# Rele_WIFI_6_Board.net
KiCad netlist of a schematic drawn in EAGLE
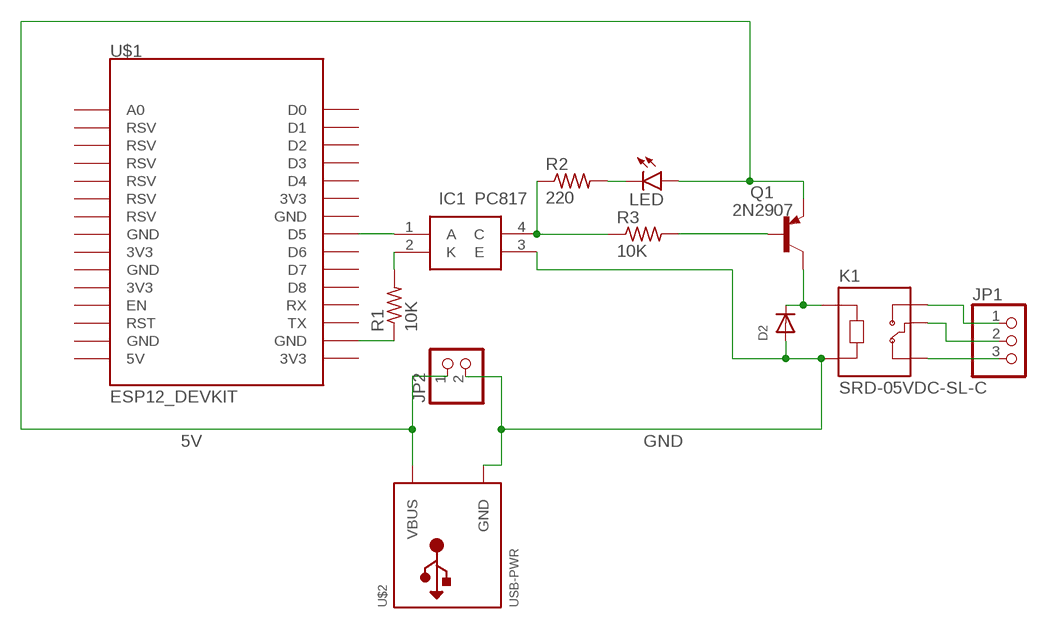
[diagram p0: schematic, sheet 1]

(export (version "E")
  (design (tool "Eeschema 10.0.6"))
  (components
    (comp (ref "D2")
      (value "DIODEDO-1N4148")
      (footprint "eagle-import:DO-1N4148")
      (libsource (lib "eagle-import") (part "DIODEDO-1N4148"))
    )
    (comp (ref "IC1")
      (value "PC817")
      (footprint "eagle-import:DIP810W60P254L460H500Q4N")
      (libsource (lib "eagle-import") (part "PC817"))
    )
    (comp (ref "JP1")
      (value "PINHD-1X3")
      (footprint "eagle-import:1X03")
      (libsource (lib "eagle-import") (part "PINHD-1X3"))
    )
    (comp (ref "JP2")
      (value "PINHD-1X2")
      (footprint "eagle-import:1X02")
      (libsource (lib "eagle-import") (part "PINHD-1X2"))
    )
    (comp (ref "K1")
      (value "SRD-05VDC-SL-C")
      (footprint "eagle-import:RELAY_SRD-05VDC-SL-C")
      (fields (field (name "MF") "Songle Relay"))
      (libsource (lib "eagle-import") (part "SRD-05VDC-SL-C"))
    )
    (comp (ref "LED")
      (value "LED5MM")
      (footprint "eagle-import:LED5MM")
      (libsource (lib "eagle-import") (part "LED5MM"))
    )
    (comp (ref "Q1")
      (value "2N2907")
      (footprint "eagle-import:TO92-EBC-OVAL")
      (libsource (lib "eagle-import") (part "2N2907"))
    )
    (comp (ref "R1")
      (value "10K")
      (footprint "eagle-import:0309_12")
      (libsource (lib "eagle-import") (part "R-US_0309/12"))
    )
    (comp (ref "R2")
      (value "220")
      (footprint "eagle-import:0309_12")
      (libsource (lib "eagle-import") (part "R-US_0309/12"))
    )
    (comp (ref "R3")
      (value "10K")
      (footprint "eagle-import:0309_12")
      (libsource (lib "eagle-import") (part "R-US_0309/12"))
    )
    (comp (ref "U$1")
      (value "ESP12_DEVKIT")
      (footprint "eagle-import:ESP12_DEVKIT")
      (libsource (lib "eagle-import") (part "ESP12_DEVKIT"))
    )
    (comp (ref "U$2")
      (value "USB-PWR")
      (footprint "eagle-import:USB-MINIB-THM-MOLEX-PWRONLY")
      (libsource (lib "eagle-import") (part "USB-PWR"))
    )
  )
  (nets
    (net (code "1") (name "/5V") (class "Default")
      (node (ref "JP2") (pin "1") (pinfunction "1_1") (pintype "passive"))
      (node (ref "LED") (pin "A") (pinfunction "A_A") (pintype "passive"))
      (node (ref "Q1") (pin "E") (pinfunction "E_E") (pintype "passive"))
      (node (ref "U$2") (pin "VBUS") (pinfunction "VBUS_VBUS") (pintype "power_in"))
    )
    (net (code "2") (name "/GND") (class "Default")
      (node (ref "D2") (pin "A") (pinfunction "A_A") (pintype "passive"))
      (node (ref "IC1") (pin "3") (pinfunction "E_3") (pintype "bidirectional"))
      (node (ref "JP2") (pin "2") (pinfunction "2_2") (pintype "passive"))
      (node (ref "K1") (pin "A2") (pinfunction "A2_A2") (pintype "passive"))
      (node (ref "U$2") (pin "GND") (pinfunction "GND_GND") (pintype "power_in"))
    )
    (net (code "3") (name "Net-(D2-PadC)") (class "Default")
      (node (ref "D2") (pin "C") (pinfunction "C_C") (pintype "passive"))
      (node (ref "K1") (pin "A1") (pinfunction "A1_A1") (pintype "passive"))
      (node (ref "Q1") (pin "C") (pinfunction "C_C") (pintype "passive"))
    )
    (net (code "4") (name "Net-(IC1-A)") (class "Default")
      (node (ref "IC1") (pin "1") (pinfunction "A_1") (pintype "bidirectional"))
      (node (ref "U$1") (pin "D5") (pinfunction "D5_D5") (pintype "bidirectional"))
    )
    (net (code "5") (name "Net-(IC1-C)") (class "Default")
      (node (ref "IC1") (pin "4") (pinfunction "C_4") (pintype "bidirectional"))
      (node (ref "R2") (pin "1") (pinfunction "1_1") (pintype "passive"))
      (node (ref "R3") (pin "1") (pinfunction "1_1") (pintype "passive"))
    )
    (net (code "6") (name "Net-(IC1-K)") (class "Default")
      (node (ref "IC1") (pin "2") (pinfunction "K_2") (pintype "bidirectional"))
      (node (ref "R1") (pin "2") (pinfunction "2_2") (pintype "passive"))
    )
    (net (code "7") (name "Net-(JP1-Pad1)") (class "Default")
      (node (ref "JP1") (pin "1") (pinfunction "1_1") (pintype "passive"))
      (node (ref "K1") (pin "NO") (pinfunction "NO_NO") (pintype "passive"))
    )
    (net (code "8") (name "Net-(JP1-Pad2)") (class "Default")
      (node (ref "JP1") (pin "2") (pinfunction "2_2") (pintype "passive"))
      (node (ref "K1") (pin "COM") (pinfunction "COM_COM") (pintype "passive"))
    )
    (net (code "9") (name "Net-(JP1-Pad3)") (class "Default")
      (node (ref "JP1") (pin "3") (pinfunction "3_3") (pintype "passive"))
      (node (ref "K1") (pin "NC") (pinfunction "NC_NC") (pintype "passive"))
    )
    (net (code "10") (name "Net-(LED-C)") (class "Default")
      (node (ref "LED") (pin "K") (pinfunction "C_K") (pintype "passive"))
      (node (ref "R2") (pin "2") (pinfunction "2_2") (pintype "passive"))
    )
    (net (code "11") (name "Net-(Q1-PadB)") (class "Default")
      (node (ref "Q1") (pin "B") (pinfunction "B_B") (pintype "passive"))
      (node (ref "R3") (pin "2") (pinfunction "2_2") (pintype "passive"))
    )
    (net (code "12") (name "Net-(R1-Pad1)") (class "Default")
      (node (ref "R1") (pin "1") (pinfunction "1_1") (pintype "passive"))
      (node (ref "U$1") (pin "GND@3") (pinfunction "GND_GND@3") (pintype "bidirectional"))
    )
    (net (code "13") (name "unconnected-(U$1-3V3-Pad3V3@0)") (class "Default")
      (node (ref "U$1") (pin "3V3@0") (pinfunction "3V3_3V3@0") (pintype "bidirectional"))
    )
    (net (code "14") (name "unconnected-(U$1-3V3-Pad3V3@1)") (class "Default")
      (node (ref "U$1") (pin "3V3@1") (pinfunction "3V3_3V3@1") (pintype "bidirectional"))
    )
    (net (code "15") (name "unconnected-(U$1-3V3-Pad3V3@2)") (class "Default")
      (node (ref "U$1") (pin "3V3@2") (pinfunction "3V3_3V3@2") (pintype "bidirectional"))
    )
    (net (code "16") (name "unconnected-(U$1-3V3-Pad3V3@3)") (class "Default")
      (node (ref "U$1") (pin "3V3@3") (pinfunction "3V3_3V3@3") (pintype "bidirectional"))
    )
    (net (code "17") (name "unconnected-(U$1-GND-PadGND@0)") (class "Default")
      (node (ref "U$1") (pin "GND@0") (pinfunction "GND_GND@0") (pintype "bidirectional"))
    )
    (net (code "18") (name "unconnected-(U$1-GND-PadGND@1)") (class "Default")
      (node (ref "U$1") (pin "GND@1") (pinfunction "GND_GND@1") (pintype "bidirectional"))
    )
    (net (code "19") (name "unconnected-(U$1-GND-PadGND@2)") (class "Default")
      (node (ref "U$1") (pin "GND@2") (pinfunction "GND_GND@2") (pintype "bidirectional"))
    )
    (net (code "20") (name "unconnected-(U$1-GND-PadGND@4)") (class "Default")
      (node (ref "U$1") (pin "GND@4") (pinfunction "GND_GND@4") (pintype "bidirectional"))
    )
    (net (code "21") (name "unconnected-(U$1-Pad5V)") (class "Default")
      (node (ref "U$1") (pin "5V") (pinfunction "5V_5V") (pintype "bidirectional"))
    )
    (net (code "22") (name "unconnected-(U$1-PadA0)") (class "Default")
      (node (ref "U$1") (pin "A0") (pinfunction "A0_A0") (pintype "bidirectional"))
    )
    (net (code "23") (name "unconnected-(U$1-PadD0)") (class "Default")
      (node (ref "U$1") (pin "D0") (pinfunction "D0_D0") (pintype "bidirectional"))
    )
    (net (code "24") (name "unconnected-(U$1-PadD1)") (class "Default")
      (node (ref "U$1") (pin "D1") (pinfunction "D1_D1") (pintype "bidirectional"))
    )
    (net (code "25") (name "unconnected-(U$1-PadD2)") (class "Default")
      (node (ref "U$1") (pin "D2") (pinfunction "D2_D2") (pintype "bidirectional"))
    )
    (net (code "26") (name "unconnected-(U$1-PadD3)") (class "Default")
      (node (ref "U$1") (pin "D3") (pinfunction "D3_D3") (pintype "bidirectional"))
    )
    (net (code "27") (name "unconnected-(U$1-PadD4)") (class "Default")
      (node (ref "U$1") (pin "D4") (pinfunction "D4_D4") (pintype "bidirectional"))
    )
    (net (code "28") (name "unconnected-(U$1-PadD6)") (class "Default")
      (node (ref "U$1") (pin "D6") (pinfunction "D6_D6") (pintype "bidirectional"))
    )
    (net (code "29") (name "unconnected-(U$1-PadD7)") (class "Default")
      (node (ref "U$1") (pin "D7") (pinfunction "D7_D7") (pintype "bidirectional"))
    )
    (net (code "30") (name "unconnected-(U$1-PadD8)") (class "Default")
      (node (ref "U$1") (pin "D8") (pinfunction "D8_D8") (pintype "bidirectional"))
    )
    (net (code "31") (name "unconnected-(U$1-PadEN)") (class "Default")
      (node (ref "U$1") (pin "EN") (pinfunction "EN_EN") (pintype "bidirectional"))
    )
    (net (code "32") (name "unconnected-(U$1-PadRST)") (class "Default")
      (node (ref "U$1") (pin "RST") (pinfunction "RST_RST") (pintype "bidirectional"))
    )
    (net (code "33") (name "unconnected-(U$1-PadRX)") (class "Default")
      (node (ref "U$1") (pin "RX") (pinfunction "RX_RX") (pintype "bidirectional"))
    )
    (net (code "34") (name "unconnected-(U$1-PadTX)") (class "Default")
      (node (ref "U$1") (pin "TX") (pinfunction "TX_TX") (pintype "bidirectional"))
    )
    (net (code "35") (name "unconnected-(U$1-RSV-PadRSV@0)") (class "Default")
      (node (ref "U$1") (pin "RSV@0") (pinfunction "RSV_RSV@0") (pintype "bidirectional"))
    )
    (net (code "36") (name "unconnected-(U$1-RSV-PadRSV@1)") (class "Default")
      (node (ref "U$1") (pin "RSV@1") (pinfunction "RSV_RSV@1") (pintype "bidirectional"))
    )
    (net (code "37") (name "unconnected-(U$1-RSV-PadRSV@2)") (class "Default")
      (node (ref "U$1") (pin "RSV@2") (pinfunction "RSV_RSV@2") (pintype "bidirectional"))
    )
    (net (code "38") (name "unconnected-(U$1-RSV-PadRSV@3)") (class "Default")
      (node (ref "U$1") (pin "RSV@3") (pinfunction "RSV_RSV@3") (pintype "bidirectional"))
    )
    (net (code "39") (name "unconnected-(U$1-RSV-PadRSV@4)") (class "Default")
      (node (ref "U$1") (pin "RSV@4") (pinfunction "RSV_RSV@4") (pintype "bidirectional"))
    )
    (net (code "40") (name "unconnected-(U$1-RSV-PadRSV@5)") (class "Default")
      (node (ref "U$1") (pin "RSV@5") (pinfunction "RSV_RSV@5") (pintype "bidirectional"))
    )
  )
)
